# analog_part.net
KiCad netlist of a schematic drawn in Altium Designer
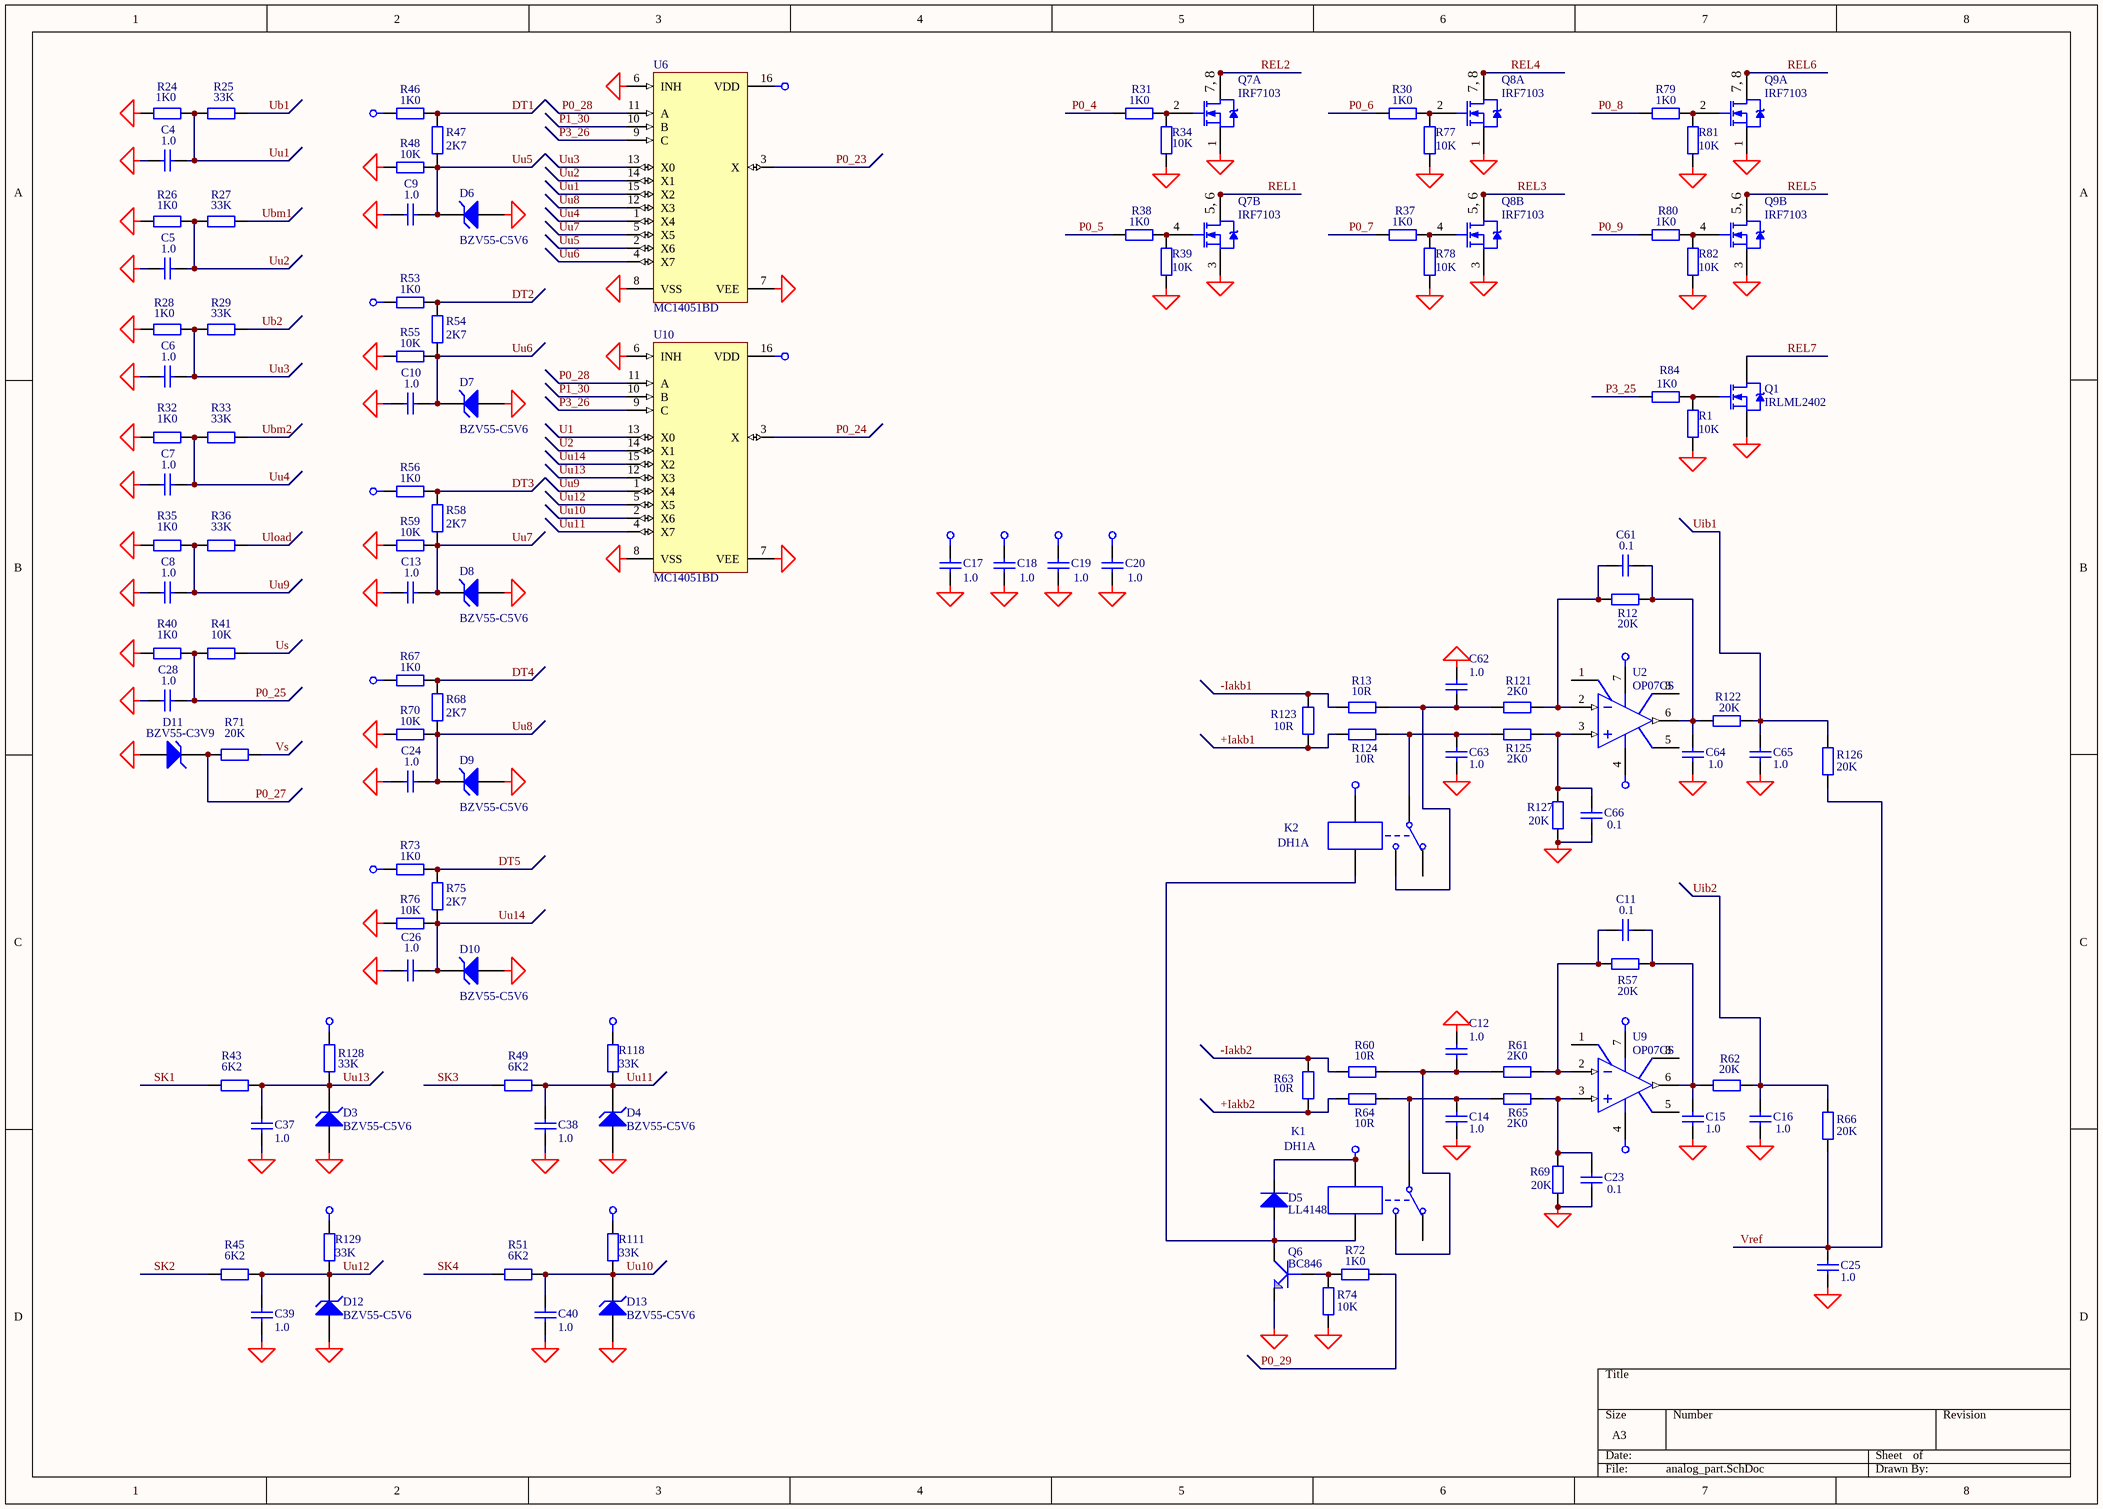
[diagram p0: analog_part.SchDoc]

(export (version "E")
  (design (tool "Eeschema 10.0.6"))
  (components
    (comp (ref "C4")
      (value "1.0")
      (footprint "_1206")
      (description "Capacitor")
      (fields (field (name "MANUFACTURER") "Generic Components"))
      (libsource (lib "Miscellaneous Devices") (part "Cap Semi"))
    )
    (comp (ref "C5")
      (value "1.0")
      (footprint "_1206")
      (description "Capacitor")
      (fields (field (name "MANUFACTURER") "Generic Components"))
      (libsource (lib "Miscellaneous Devices") (part "Cap Semi"))
    )
    (comp (ref "C6")
      (value "1.0")
      (footprint "_1206")
      (description "Capacitor")
      (fields (field (name "MANUFACTURER") "Generic Components"))
      (libsource (lib "Miscellaneous Devices") (part "Cap Semi"))
    )
    (comp (ref "C7")
      (value "1.0")
      (footprint "_1206")
      (description "Capacitor")
      (fields (field (name "MANUFACTURER") "Generic Components"))
      (libsource (lib "Miscellaneous Devices") (part "Cap Semi"))
    )
    (comp (ref "C8")
      (value "1.0")
      (footprint "_1206")
      (description "Capacitor")
      (fields (field (name "MANUFACTURER") "Generic Components"))
      (libsource (lib "Miscellaneous Devices") (part "Cap Semi"))
    )
    (comp (ref "C9")
      (value "1.0")
      (footprint "_1206")
      (description "Capacitor")
      (fields (field (name "MANUFACTURER") "Generic Components"))
      (libsource (lib "Miscellaneous Devices") (part "Cap Semi"))
    )
    (comp (ref "C10")
      (value "1.0")
      (footprint "_1206")
      (description "Capacitor")
      (fields (field (name "MANUFACTURER") "Generic Components"))
      (libsource (lib "Miscellaneous Devices") (part "Cap Semi"))
    )
    (comp (ref "C11")
      (value "0.1")
      (footprint "_1206")
      (description "Capacitor")
      (fields (field (name "MANUFACTURER") "Generic Components"))
      (libsource (lib "Miscellaneous Devices") (part "Cap Semi"))
    )
    (comp (ref "C12")
      (value "1.0")
      (footprint "_1206")
      (description "Capacitor")
      (fields (field (name "MANUFACTURER") "Generic Components"))
      (libsource (lib "Miscellaneous Devices") (part "Cap Semi"))
    )
    (comp (ref "C13")
      (value "1.0")
      (footprint "_1206")
      (description "Capacitor")
      (fields (field (name "MANUFACTURER") "Generic Components"))
      (libsource (lib "Miscellaneous Devices") (part "Cap Semi"))
    )
    (comp (ref "C14")
      (value "1.0")
      (footprint "_1206")
      (description "Capacitor")
      (fields (field (name "MANUFACTURER") "Generic Components"))
      (libsource (lib "Miscellaneous Devices") (part "Cap Semi"))
    )
    (comp (ref "C15")
      (value "1.0")
      (footprint "_1206")
      (description "Capacitor")
      (fields (field (name "MANUFACTURER") "Generic Components"))
      (libsource (lib "Miscellaneous Devices") (part "Cap Semi"))
    )
    (comp (ref "C16")
      (value "1.0")
      (footprint "_1206")
      (description "Capacitor")
      (fields (field (name "MANUFACTURER") "Generic Components"))
      (libsource (lib "Miscellaneous Devices") (part "Cap Semi"))
    )
    (comp (ref "C17")
      (value "1.0")
      (footprint "_1206")
      (description "Capacitor")
      (fields (field (name "MANUFACTURER") "Generic Components"))
      (libsource (lib "Miscellaneous Devices") (part "Cap Semi"))
    )
    (comp (ref "C18")
      (value "1.0")
      (footprint "_1206")
      (description "Capacitor")
      (fields (field (name "MANUFACTURER") "Generic Components"))
      (libsource (lib "Miscellaneous Devices") (part "Cap Semi"))
    )
    (comp (ref "C19")
      (value "1.0")
      (footprint "_1206")
      (description "Capacitor")
      (fields (field (name "MANUFACTURER") "Generic Components"))
      (libsource (lib "Miscellaneous Devices") (part "Cap Semi"))
    )
    (comp (ref "C20")
      (value "1.0")
      (footprint "_1206")
      (description "Capacitor")
      (fields (field (name "MANUFACTURER") "Generic Components"))
      (libsource (lib "Miscellaneous Devices") (part "Cap Semi"))
    )
    (comp (ref "C23")
      (value "0.1")
      (footprint "_1206")
      (description "Capacitor")
      (fields (field (name "MANUFACTURER") "Generic Components"))
      (libsource (lib "Miscellaneous Devices") (part "Cap Semi"))
    )
    (comp (ref "C24")
      (value "1.0")
      (footprint "_1206")
      (description "Capacitor")
      (fields (field (name "MANUFACTURER") "Generic Components"))
      (libsource (lib "Miscellaneous Devices") (part "Cap Semi"))
    )
    (comp (ref "C25")
      (value "1.0")
      (footprint "_1206")
      (description "Capacitor")
      (fields (field (name "MANUFACTURER") "Generic Components"))
      (libsource (lib "Miscellaneous Devices") (part "Cap Semi"))
    )
    (comp (ref "C26")
      (value "1.0")
      (footprint "_1206")
      (description "Capacitor")
      (fields (field (name "MANUFACTURER") "Generic Components"))
      (libsource (lib "Miscellaneous Devices") (part "Cap Semi"))
    )
    (comp (ref "C28")
      (value "1.0")
      (footprint "_1206")
      (description "Capacitor")
      (fields (field (name "MANUFACTURER") "Generic Components"))
      (libsource (lib "Miscellaneous Devices") (part "Cap Semi"))
    )
    (comp (ref "C37")
      (value "1.0")
      (footprint "_1206")
      (description "Capacitor")
      (fields (field (name "MANUFACTURER") "Generic Components"))
      (libsource (lib "Miscellaneous Devices") (part "Cap Semi"))
    )
    (comp (ref "C38")
      (value "1.0")
      (footprint "_1206")
      (description "Capacitor")
      (fields (field (name "MANUFACTURER") "Generic Components"))
      (libsource (lib "Miscellaneous Devices") (part "Cap Semi"))
    )
    (comp (ref "C39")
      (value "1.0")
      (footprint "_1206")
      (description "Capacitor")
      (fields (field (name "MANUFACTURER") "Generic Components"))
      (libsource (lib "Miscellaneous Devices") (part "Cap Semi"))
    )
    (comp (ref "C40")
      (value "1.0")
      (footprint "_1206")
      (description "Capacitor")
      (fields (field (name "MANUFACTURER") "Generic Components"))
      (libsource (lib "Miscellaneous Devices") (part "Cap Semi"))
    )
    (comp (ref "C61")
      (value "0.1")
      (footprint "_1206")
      (description "Capacitor")
      (fields (field (name "MANUFACTURER") "Generic Components"))
      (libsource (lib "Miscellaneous Devices") (part "Cap Semi"))
    )
    (comp (ref "C62")
      (value "1.0")
      (footprint "_1206")
      (description "Capacitor")
      (fields (field (name "MANUFACTURER") "Generic Components"))
      (libsource (lib "Miscellaneous Devices") (part "Cap Semi"))
    )
    (comp (ref "C63")
      (value "1.0")
      (footprint "_1206")
      (description "Capacitor")
      (fields (field (name "MANUFACTURER") "Generic Components"))
      (libsource (lib "Miscellaneous Devices") (part "Cap Semi"))
    )
    (comp (ref "C64")
      (value "1.0")
      (footprint "_1206")
      (description "Capacitor")
      (fields (field (name "MANUFACTURER") "Generic Components"))
      (libsource (lib "Miscellaneous Devices") (part "Cap Semi"))
    )
    (comp (ref "C65")
      (value "1.0")
      (footprint "_1206")
      (description "Capacitor")
      (fields (field (name "MANUFACTURER") "Generic Components"))
      (libsource (lib "Miscellaneous Devices") (part "Cap Semi"))
    )
    (comp (ref "C66")
      (value "0.1")
      (footprint "_1206")
      (description "Capacitor")
      (fields (field (name "MANUFACTURER") "Generic Components"))
      (libsource (lib "Miscellaneous Devices") (part "Cap Semi"))
    )
    (comp (ref "D3")
      (value "BZV55-C5V6")
      (footprint "_1206d")
      (description "Zener Diode")
      (fields (field (name "MANUFACTURER") "Generic Components"))
      (libsource (lib "Miscellaneous Devices") (part "D Zener"))
    )
    (comp (ref "D4")
      (value "BZV55-C5V6")
      (footprint "_1206d")
      (description "Zener Diode")
      (fields (field (name "MANUFACTURER") "Generic Components"))
      (libsource (lib "Miscellaneous Devices") (part "D Zener"))
    )
    (comp (ref "D5")
      (value "LL4148")
      (footprint "_1206d")
      (description "Diode")
      (fields (field (name "MANUFACTURER") "Generic Components"))
      (libsource (lib "Pal") (part "Diode"))
    )
    (comp (ref "D6")
      (value "BZV55-C5V6")
      (footprint "_1206d")
      (description "Zener Diode")
      (fields (field (name "MANUFACTURER") "Generic Components"))
      (libsource (lib "Miscellaneous Devices") (part "D Zener"))
    )
    (comp (ref "D7")
      (value "BZV55-C5V6")
      (footprint "_1206d")
      (description "Zener Diode")
      (fields (field (name "MANUFACTURER") "Generic Components"))
      (libsource (lib "Miscellaneous Devices") (part "D Zener"))
    )
    (comp (ref "D8")
      (value "BZV55-C5V6")
      (footprint "_1206d")
      (description "Zener Diode")
      (fields (field (name "MANUFACTURER") "Generic Components"))
      (libsource (lib "Miscellaneous Devices") (part "D Zener"))
    )
    (comp (ref "D9")
      (value "BZV55-C5V6")
      (footprint "_1206d")
      (description "Zener Diode")
      (fields (field (name "MANUFACTURER") "Generic Components"))
      (libsource (lib "Miscellaneous Devices") (part "D Zener"))
    )
    (comp (ref "D10")
      (value "BZV55-C5V6")
      (footprint "_1206d")
      (description "Zener Diode")
      (fields (field (name "MANUFACTURER") "Generic Components"))
      (libsource (lib "Miscellaneous Devices") (part "D Zener"))
    )
    (comp (ref "D11")
      (value "BZV55-C3V9")
      (footprint "_1206d")
      (description "Zener Diode")
      (fields (field (name "MANUFACTURER") "Generic Components"))
      (libsource (lib "Miscellaneous Devices") (part "D Zener"))
    )
    (comp (ref "D12")
      (value "BZV55-C5V6")
      (footprint "_1206d")
      (description "Zener Diode")
      (fields (field (name "MANUFACTURER") "Generic Components"))
      (libsource (lib "Miscellaneous Devices") (part "D Zener"))
    )
    (comp (ref "D13")
      (value "BZV55-C5V6")
      (footprint "_1206d")
      (description "Zener Diode")
      (fields (field (name "MANUFACTURER") "Generic Components"))
      (libsource (lib "Miscellaneous Devices") (part "D Zener"))
    )
    (comp (ref "K1")
      (value "DH1A")
      (footprint "kuan")
      (description "Relay")
      (fields (field (name "MANUFACTURER") "Generic Components"))
      (libsource (lib "PAL") (part "BS115"))
    )
    (comp (ref "K2")
      (value "DH1A")
      (footprint "kuan")
      (description "Relay")
      (fields (field (name "MANUFACTURER") "Generic Components"))
      (libsource (lib "PAL") (part "BS115"))
    )
    (comp (ref "Q1")
      (value "IRLML2402")
      (footprint "SO-G3/Z3.3")
      (description "HEXFET Power MOSFET")
      (fields (field (name "MANUFACTURER") "International Rectifier"))
      (libsource (lib "IR Discrete MOSFET") (part "IRLML2402"))
    )
    (comp (ref "Q6")
      (value "BC846")
      (footprint "SO-G3")
      (description "Bipolar transistor")
      (libsource (lib "MAIN") (part "GT122"))
    )
    (comp (ref "Q7")
      (value "IRF7103")
      (footprint "SO-G8/Y2.2")
      (description "FET")
      (fields (field (name "MANUFACTURER") "International Rectifier"))
      (libsource (lib "IR Discrete MOSFET") (part "IRF7301"))
    )
    (comp (ref "Q8")
      (value "IRF7103")
      (footprint "SO-G8/Y2.2")
      (description "FET")
      (fields (field (name "MANUFACTURER") "International Rectifier"))
      (libsource (lib "IR Discrete MOSFET") (part "IRF7301"))
    )
    (comp (ref "Q9")
      (value "IRF7103")
      (footprint "SO-G8/Y2.2")
      (description "FET")
      (fields (field (name "MANUFACTURER") "International Rectifier"))
      (libsource (lib "IR Discrete MOSFET") (part "IRF7301"))
    )
    (comp (ref "R1")
      (value "10K")
      (footprint "_1206")
      (description "Resistor")
      (fields (field (name "MANUFACTURER") "Generic Components"))
      (libsource (lib "") (part "Res2_1"))
    )
    (comp (ref "R12")
      (value "20K")
      (footprint "_1206")
      (description "Resistor")
      (fields (field (name "MANUFACTURER") "Generic Components"))
      (libsource (lib "Miscellaneous Devices") (part "Res2"))
    )
    (comp (ref "R13")
      (value "10R")
      (footprint "_1206")
      (description "Resistor")
      (fields (field (name "MANUFACTURER") "Generic Components"))
      (libsource (lib "") (part "Res2_2"))
    )
    (comp (ref "R24")
      (value "1K0")
      (footprint "_1206")
      (description "Resistor")
      (fields (field (name "MANUFACTURER") "Generic Components"))
      (libsource (lib "") (part "Res2_2"))
    )
    (comp (ref "R25")
      (value "33K")
      (footprint "_1206")
      (description "Resistor")
      (fields (field (name "MANUFACTURER") "Generic Components"))
      (libsource (lib "Miscellaneous Devices") (part "Res2"))
    )
    (comp (ref "R26")
      (value "1K0")
      (footprint "_1206")
      (description "Resistor")
      (fields (field (name "MANUFACTURER") "Generic Components"))
      (libsource (lib "") (part "Res2_2"))
    )
    (comp (ref "R27")
      (value "33K")
      (footprint "_1206")
      (description "Resistor")
      (fields (field (name "MANUFACTURER") "Generic Components"))
      (libsource (lib "Miscellaneous Devices") (part "Res2"))
    )
    (comp (ref "R28")
      (value "1K0")
      (footprint "_1206")
      (description "Resistor")
      (fields (field (name "MANUFACTURER") "Generic Components"))
      (libsource (lib "") (part "Res2_2"))
    )
    (comp (ref "R29")
      (value "33K")
      (footprint "_1206")
      (description "Resistor")
      (fields (field (name "MANUFACTURER") "Generic Components"))
      (libsource (lib "Miscellaneous Devices") (part "Res2"))
    )
    (comp (ref "R30")
      (value "1K0")
      (footprint "_1206")
      (description "Resistor")
      (fields (field (name "MANUFACTURER") "Generic Components"))
      (libsource (lib "Miscellaneous Devices") (part "Res2"))
    )
    (comp (ref "R31")
      (value "1K0")
      (footprint "_1206")
      (description "Resistor")
      (fields (field (name "MANUFACTURER") "Generic Components"))
      (libsource (lib "Miscellaneous Devices") (part "Res2"))
    )
    (comp (ref "R32")
      (value "1K0")
      (footprint "_1206")
      (description "Resistor")
      (fields (field (name "MANUFACTURER") "Generic Components"))
      (libsource (lib "") (part "Res2_2"))
    )
    (comp (ref "R33")
      (value "33K")
      (footprint "_1206")
      (description "Resistor")
      (fields (field (name "MANUFACTURER") "Generic Components"))
      (libsource (lib "Miscellaneous Devices") (part "Res2"))
    )
    (comp (ref "R34")
      (value "10K")
      (footprint "_1206")
      (description "Resistor")
      (fields (field (name "MANUFACTURER") "Generic Components"))
      (libsource (lib "") (part "Res2_1"))
    )
    (comp (ref "R35")
      (value "1K0")
      (footprint "_1206")
      (description "Resistor")
      (fields (field (name "MANUFACTURER") "Generic Components"))
      (libsource (lib "") (part "Res2_2"))
    )
    (comp (ref "R36")
      (value "33K")
      (footprint "_1206")
      (description "Resistor")
      (fields (field (name "MANUFACTURER") "Generic Components"))
      (libsource (lib "Miscellaneous Devices") (part "Res2"))
    )
    (comp (ref "R37")
      (value "1K0")
      (footprint "_1206")
      (description "Resistor")
      (fields (field (name "MANUFACTURER") "Generic Components") (field (name "ALTIUM_VALUE") "1K0"))
      (libsource (lib "Miscellaneous Devices") (part "Res2"))
    )
    (comp (ref "R38")
      (value "1K0")
      (footprint "_1206")
      (description "Resistor")
      (fields (field (name "MANUFACTURER") "Generic Components"))
      (libsource (lib "Miscellaneous Devices") (part "Res2"))
    )
    (comp (ref "R39")
      (value "10K")
      (footprint "_1206")
      (description "Resistor")
      (fields (field (name "MANUFACTURER") "Generic Components"))
      (libsource (lib "") (part "Res2_1"))
    )
    (comp (ref "R40")
      (value "1K0")
      (footprint "_1206")
      (description "Resistor")
      (fields (field (name "MANUFACTURER") "Generic Components"))
      (libsource (lib "") (part "Res2_2"))
    )
    (comp (ref "R41")
      (value "10K")
      (footprint "_1206")
      (description "Resistor")
      (fields (field (name "MANUFACTURER") "Generic Components"))
      (libsource (lib "Miscellaneous Devices") (part "Res2"))
    )
    (comp (ref "R43")
      (value "6K2")
      (footprint "_1206")
      (description "Resistor")
      (fields (field (name "MANUFACTURER") "Generic Components"))
      (libsource (lib "Miscellaneous Devices") (part "Res2"))
    )
    (comp (ref "R45")
      (value "6K2")
      (footprint "_1206")
      (description "Resistor")
      (fields (field (name "MANUFACTURER") "Generic Components"))
      (libsource (lib "Miscellaneous Devices") (part "Res2"))
    )
    (comp (ref "R46")
      (value "1K0")
      (footprint "_0805")
      (description "Resistor")
      (fields (field (name "MANUFACTURER") "Generic Components"))
      (libsource (lib "") (part "Res2_2"))
    )
    (comp (ref "R47")
      (value "2K7")
      (footprint "_1206")
      (description "Resistor")
      (fields (field (name "MANUFACTURER") "Generic Components"))
      (libsource (lib "") (part "Res2_3"))
    )
    (comp (ref "R48")
      (value "10K")
      (footprint "_1206")
      (description "Resistor")
      (fields (field (name "MANUFACTURER") "Generic Components"))
      (libsource (lib "Miscellaneous Devices") (part "Res2"))
    )
    (comp (ref "R49")
      (value "6K2")
      (footprint "_1206")
      (description "Resistor")
      (fields (field (name "MANUFACTURER") "Generic Components"))
      (libsource (lib "Miscellaneous Devices") (part "Res2"))
    )
    (comp (ref "R51")
      (value "6K2")
      (footprint "_1206")
      (description "Resistor")
      (fields (field (name "MANUFACTURER") "Generic Components"))
      (libsource (lib "Miscellaneous Devices") (part "Res2"))
    )
    (comp (ref "R53")
      (value "1K0")
      (footprint "_0805")
      (description "Resistor")
      (fields (field (name "MANUFACTURER") "Generic Components") (field (name "ALTIUM_VALUE") "1K0"))
      (libsource (lib "") (part "Res2_2"))
    )
    (comp (ref "R54")
      (value "2K7")
      (footprint "_1206")
      (description "Resistor")
      (fields (field (name "MANUFACTURER") "Generic Components"))
      (libsource (lib "") (part "Res2_3"))
    )
    (comp (ref "R55")
      (value "10K")
      (footprint "_1206")
      (description "Resistor")
      (fields (field (name "MANUFACTURER") "Generic Components"))
      (libsource (lib "Miscellaneous Devices") (part "Res2"))
    )
    (comp (ref "R56")
      (value "1K0")
      (footprint "_0805")
      (description "Resistor")
      (fields (field (name "MANUFACTURER") "Generic Components") (field (name "ALTIUM_VALUE") "1K0"))
      (libsource (lib "") (part "Res2_2"))
    )
    (comp (ref "R57")
      (value "20K")
      (footprint "_1206")
      (description "Resistor")
      (fields (field (name "MANUFACTURER") "Generic Components"))
      (libsource (lib "Miscellaneous Devices") (part "Res2"))
    )
    (comp (ref "R58")
      (value "2K7")
      (footprint "_1206")
      (description "Resistor")
      (fields (field (name "MANUFACTURER") "Generic Components"))
      (libsource (lib "") (part "Res2_3"))
    )
    (comp (ref "R59")
      (value "10K")
      (footprint "_1206")
      (description "Resistor")
      (fields (field (name "MANUFACTURER") "Generic Components"))
      (libsource (lib "Miscellaneous Devices") (part "Res2"))
    )
    (comp (ref "R60")
      (value "10R")
      (footprint "_1206")
      (description "Resistor")
      (fields (field (name "MANUFACTURER") "Generic Components"))
      (libsource (lib "") (part "Res2_2"))
    )
    (comp (ref "R61")
      (value "2K0")
      (footprint "_1206")
      (description "Resistor")
      (fields (field (name "MANUFACTURER") "Generic Components"))
      (libsource (lib "Miscellaneous Devices") (part "Res2"))
    )
    (comp (ref "R62")
      (value "20K")
      (footprint "_1206")
      (description "Resistor")
      (fields (field (name "MANUFACTURER") "Generic Components"))
      (libsource (lib "Miscellaneous Devices") (part "Res2"))
    )
    (comp (ref "R63")
      (value "10R")
      (footprint "_1206")
      (description "Resistor")
      (fields (field (name "MANUFACTURER") "Generic Components"))
      (libsource (lib "") (part "Res2_1"))
    )
    (comp (ref "R64")
      (value "10R")
      (footprint "_1206")
      (description "Resistor")
      (fields (field (name "MANUFACTURER") "Generic Components"))
      (libsource (lib "") (part "Res2_2"))
    )
    (comp (ref "R65")
      (value "2K0")
      (footprint "_1206")
      (description "Resistor")
      (fields (field (name "MANUFACTURER") "Generic Components"))
      (libsource (lib "Miscellaneous Devices") (part "Res2"))
    )
    (comp (ref "R66")
      (value "20K")
      (footprint "_1206")
      (description "Resistor")
      (fields (field (name "MANUFACTURER") "Generic Components"))
      (libsource (lib "") (part "Res2_2"))
    )
    (comp (ref "R67")
      (value "1K0")
      (footprint "_0805")
      (description "Resistor")
      (fields (field (name "MANUFACTURER") "Generic Components") (field (name "ALTIUM_VALUE") "1K0"))
      (libsource (lib "") (part "Res2_2"))
    )
    (comp (ref "R68")
      (value "2K7")
      (footprint "_1206")
      (description "Resistor")
      (fields (field (name "MANUFACTURER") "Generic Components"))
      (libsource (lib "") (part "Res2_3"))
    )
    (comp (ref "R69")
      (value "20K")
      (footprint "_1206")
      (description "Resistor")
      (fields (field (name "MANUFACTURER") "Generic Components"))
      (libsource (lib "") (part "Res2_1"))
    )
    (comp (ref "R70")
      (value "10K")
      (footprint "_1206")
      (description "Resistor")
      (fields (field (name "MANUFACTURER") "Generic Components"))
      (libsource (lib "Miscellaneous Devices") (part "Res2"))
    )
    (comp (ref "R71")
      (value "20K")
      (footprint "_1206")
      (description "Resistor")
      (fields (field (name "MANUFACTURER") "Generic Components"))
      (libsource (lib "Miscellaneous Devices") (part "Res2"))
    )
    (comp (ref "R72")
      (value "1K0")
      (footprint "_1206")
      (description "Resistor")
      (fields (field (name "MANUFACTURER") "Generic Components"))
      (libsource (lib "") (part "Res2_3"))
    )
    (comp (ref "R73")
      (value "1K0")
      (footprint "_0805")
      (description "Resistor")
      (fields (field (name "MANUFACTURER") "Generic Components") (field (name "ALTIUM_VALUE") "1K0"))
      (libsource (lib "") (part "Res2_2"))
    )
    (comp (ref "R74")
      (value "10K")
      (footprint "_1206")
      (description "Resistor")
      (fields (field (name "MANUFACTURER") "Generic Components"))
      (libsource (lib "Miscellaneous Devices") (part "Res2"))
    )
    (comp (ref "R75")
      (value "2K7")
      (footprint "_1206")
      (description "Resistor")
      (fields (field (name "MANUFACTURER") "Generic Components"))
      (libsource (lib "") (part "Res2_3"))
    )
    (comp (ref "R76")
      (value "10K")
      (footprint "_1206")
      (description "Resistor")
      (fields (field (name "MANUFACTURER") "Generic Components"))
      (libsource (lib "Miscellaneous Devices") (part "Res2"))
    )
    (comp (ref "R77")
      (value "10K")
      (footprint "_1206")
      (description "Resistor")
      (fields (field (name "MANUFACTURER") "Generic Components"))
      (libsource (lib "") (part "Res2_1"))
    )
    (comp (ref "R78")
      (value "10K")
      (footprint "_1206")
      (description "Resistor")
      (fields (field (name "MANUFACTURER") "Generic Components"))
      (libsource (lib "") (part "Res2_1"))
    )
    (comp (ref "R79")
      (value "1K0")
      (footprint "_1206")
      (description "Resistor")
      (fields (field (name "MANUFACTURER") "Generic Components"))
      (libsource (lib "Miscellaneous Devices") (part "Res2"))
    )
    (comp (ref "R80")
      (value "1K0")
      (footprint "_1206")
      (description "Resistor")
      (fields (field (name "MANUFACTURER") "Generic Components") (field (name "ALTIUM_VALUE") "1K0"))
      (libsource (lib "Miscellaneous Devices") (part "Res2"))
    )
    (comp (ref "R81")
      (value "10K")
      (footprint "_1206")
      (description "Resistor")
      (fields (field (name "MANUFACTURER") "Generic Components"))
      (libsource (lib "") (part "Res2_1"))
    )
    (comp (ref "R82")
      (value "10K")
      (footprint "_1206")
      (description "Resistor")
      (fields (field (name "MANUFACTURER") "Generic Components"))
      (libsource (lib "") (part "Res2_1"))
    )
    (comp (ref "R84")
      (value "1K0")
      (footprint "_1206")
      (description "Resistor")
      (fields (field (name "MANUFACTURER") "Generic Components"))
      (libsource (lib "Miscellaneous Devices") (part "Res2"))
    )
    (comp (ref "R111")
      (value "33K")
      (footprint "_1206")
      (description "Resistor")
      (fields (field (name "MANUFACTURER") "Generic Components"))
      (libsource (lib "") (part "Res2_2"))
    )
    (comp (ref "R118")
      (value "33K")
      (footprint "_1206")
      (description "Resistor")
      (fields (field (name "MANUFACTURER") "Generic Components"))
      (libsource (lib "") (part "Res2_2"))
    )
    (comp (ref "R121")
      (value "2K0")
      (footprint "_1206")
      (description "Resistor")
      (fields (field (name "MANUFACTURER") "Generic Components"))
      (libsource (lib "Miscellaneous Devices") (part "Res2"))
    )
    (comp (ref "R122")
      (value "20K")
      (footprint "_1206")
      (description "Resistor")
      (fields (field (name "MANUFACTURER") "Generic Components"))
      (libsource (lib "Miscellaneous Devices") (part "Res2"))
    )
    (comp (ref "R123")
      (value "10R")
      (footprint "_1206")
      (description "Resistor")
      (fields (field (name "MANUFACTURER") "Generic Components"))
      (libsource (lib "") (part "Res2_1"))
    )
    (comp (ref "R124")
      (value "10R")
      (footprint "_1206")
      (description "Resistor")
      (fields (field (name "MANUFACTURER") "Generic Components"))
      (libsource (lib "") (part "Res2_2"))
    )
    (comp (ref "R125")
      (value "2K0")
      (footprint "_1206")
      (description "Resistor")
      (fields (field (name "MANUFACTURER") "Generic Components"))
      (libsource (lib "Miscellaneous Devices") (part "Res2"))
    )
    (comp (ref "R126")
      (value "20K")
      (footprint "_1206")
      (description "Resistor")
      (fields (field (name "MANUFACTURER") "Generic Components"))
      (libsource (lib "") (part "Res2_2"))
    )
    (comp (ref "R127")
      (value "20K")
      (footprint "_1206")
      (description "Resistor")
      (fields (field (name "MANUFACTURER") "Generic Components"))
      (libsource (lib "") (part "Res2_1"))
    )
    (comp (ref "R128")
      (value "33K")
      (footprint "_1206")
      (description "Resistor")
      (fields (field (name "MANUFACTURER") "Generic Components"))
      (libsource (lib "") (part "Res2_3"))
    )
    (comp (ref "R129")
      (value "33K")
      (footprint "_1206")
      (description "Resistor")
      (fields (field (name "MANUFACTURER") "Generic Components"))
      (libsource (lib "") (part "Res2_2"))
    )
    (comp (ref "U2")
      (value "OP07CS")
      (footprint "SO-G8")
      (description "Operational Amplifier")
      (fields (field (name "MANUFACTURER") "Analog Devices"))
      (libsource (lib "AD Operational Amplifier") (part "OP07CS"))
    )
    (comp (ref "U6")
      (value "MC14051BD")
      (footprint "SO-G16/C5.85")
      (description "Multiplexer")
      (fields (field (name "MANUFACTURER") "ON Semiconductor"))
      (libsource (lib "ON Semi Logic Multiplexer") (part "MC14051BD"))
    )
    (comp (ref "U9")
      (value "OP07CS")
      (footprint "SO-G8")
      (description "Operational Amplifier")
      (fields (field (name "MANUFACTURER") "Analog Devices"))
      (libsource (lib "AD Operational Amplifier") (part "OP07CS"))
    )
    (comp (ref "U10")
      (value "MC14051BD")
      (footprint "SO-G16/C5.85")
      (description "Multiplexer")
      (fields (field (name "MANUFACTURER") "ON Semiconductor"))
      (libsource (lib "ON Semi Logic Multiplexer") (part "MC14051BD"))
    )
  )
  (nets
    (net (code "1") (name "+3v3") (class "Default")
      (node (ref "R111") (pin "1") (pinfunction "1_1") (pintype "passive"))
      (node (ref "R118") (pin "1") (pinfunction "1_1") (pintype "passive"))
      (node (ref "R128") (pin "1") (pinfunction "1_1") (pintype "passive"))
      (node (ref "R129") (pin "1") (pinfunction "1_1") (pintype "passive"))
    )
    (net (code "2") (name "+5v") (class "Default")
      (node (ref "C17") (pin "2") (pinfunction "2_2") (pintype "passive"))
      (node (ref "C19") (pin "2") (pinfunction "2_2") (pintype "passive"))
      (node (ref "D5") (pin "2") (pinfunction "K_2") (pintype "passive"))
      (node (ref "K1") (pin "4") (pinfunction "4_4") (pintype "passive"))
      (node (ref "K2") (pin "4") (pinfunction "4_4") (pintype "passive"))
      (node (ref "R46") (pin "2") (pinfunction "2_2") (pintype "passive"))
      (node (ref "R53") (pin "2") (pinfunction "2_2") (pintype "passive"))
      (node (ref "R56") (pin "2") (pinfunction "2_2") (pintype "passive"))
      (node (ref "R67") (pin "2") (pinfunction "2_2") (pintype "passive"))
      (node (ref "R73") (pin "2") (pinfunction "2_2") (pintype "passive"))
      (node (ref "U10") (pin "16") (pinfunction "VDD_16") (pintype "power_in"))
      (node (ref "U2") (pin "7") (pinfunction "V+_7") (pintype "power_in"))
      (node (ref "U6") (pin "16") (pinfunction "VDD_16") (pintype "power_in"))
      (node (ref "U9") (pin "7") (pinfunction "V+_7") (pintype "power_in"))
    )
    (net (code "3") (name "-5v") (class "Default")
      (node (ref "C18") (pin "2") (pinfunction "2_2") (pintype "passive"))
      (node (ref "U2") (pin "4") (pinfunction "V-_4") (pintype "power_in"))
      (node (ref "U9") (pin "4") (pinfunction "V-_4") (pintype "power_in"))
    )
    (net (code "4") (name "/+Iakb1") (class "Default")
      (node (ref "R123") (pin "1") (pinfunction "1_1") (pintype "passive"))
      (node (ref "R124") (pin "2") (pinfunction "2_2") (pintype "passive"))
    )
    (net (code "5") (name "/+Iakb2") (class "Default")
      (node (ref "R63") (pin "1") (pinfunction "1_1") (pintype "passive"))
      (node (ref "R64") (pin "2") (pinfunction "2_2") (pintype "passive"))
    )
    (net (code "6") (name "/-Iakb1") (class "Default")
      (node (ref "R123") (pin "2") (pinfunction "2_2") (pintype "passive"))
      (node (ref "R13") (pin "2") (pinfunction "2_2") (pintype "passive"))
    )
    (net (code "7") (name "/-Iakb2") (class "Default")
      (node (ref "R60") (pin "2") (pinfunction "2_2") (pintype "passive"))
      (node (ref "R63") (pin "2") (pinfunction "2_2") (pintype "passive"))
    )
    (net (code "8") (name "/DT1") (class "Default")
      (node (ref "R46") (pin "1") (pinfunction "1_1") (pintype "passive"))
      (node (ref "R47") (pin "1") (pinfunction "1_1") (pintype "passive"))
    )
    (net (code "9") (name "/DT2") (class "Default")
      (node (ref "R53") (pin "1") (pinfunction "1_1") (pintype "passive"))
      (node (ref "R54") (pin "1") (pinfunction "1_1") (pintype "passive"))
    )
    (net (code "10") (name "/DT3") (class "Default")
      (node (ref "R56") (pin "1") (pinfunction "1_1") (pintype "passive"))
      (node (ref "R58") (pin "1") (pinfunction "1_1") (pintype "passive"))
    )
    (net (code "11") (name "/DT4") (class "Default")
      (node (ref "R67") (pin "1") (pinfunction "1_1") (pintype "passive"))
      (node (ref "R68") (pin "1") (pinfunction "1_1") (pintype "passive"))
    )
    (net (code "12") (name "/DT5") (class "Default")
      (node (ref "R73") (pin "1") (pinfunction "1_1") (pintype "passive"))
      (node (ref "R75") (pin "1") (pinfunction "1_1") (pintype "passive"))
    )
    (net (code "13") (name "/P0_4") (class "Default")
      (node (ref "R31") (pin "1") (pinfunction "1_1") (pintype "passive"))
    )
    (net (code "14") (name "/P0_5") (class "Default")
      (node (ref "R38") (pin "1") (pinfunction "1_1") (pintype "passive"))
    )
    (net (code "15") (name "/P0_6") (class "Default")
      (node (ref "R30") (pin "1") (pinfunction "1_1") (pintype "passive"))
    )
    (net (code "16") (name "/P0_7") (class "Default")
      (node (ref "R37") (pin "1") (pinfunction "1_1") (pintype "passive"))
    )
    (net (code "17") (name "/P0_8") (class "Default")
      (node (ref "R79") (pin "1") (pinfunction "1_1") (pintype "passive"))
    )
    (net (code "18") (name "/P0_9") (class "Default")
      (node (ref "R80") (pin "1") (pinfunction "1_1") (pintype "passive"))
    )
    (net (code "19") (name "/P0_23") (class "Default")
      (node (ref "U6") (pin "3") (pinfunction "X_3") (pintype "bidirectional"))
    )
    (net (code "20") (name "/P0_24") (class "Default")
      (node (ref "U10") (pin "3") (pinfunction "X_3") (pintype "bidirectional"))
    )
    (net (code "21") (name "/P0_25") (class "Default")
      (node (ref "C28") (pin "1") (pinfunction "1_1") (pintype "passive"))
      (node (ref "R40") (pin "1") (pinfunction "1_1") (pintype "passive"))
      (node (ref "R41") (pin "1") (pinfunction "1_1") (pintype "passive"))
    )
    (net (code "22") (name "/P0_27") (class "Default")
      (node (ref "D11") (pin "2") (pinfunction "K_2") (pintype "passive"))
      (node (ref "R71") (pin "1") (pinfunction "1_1") (pintype "passive"))
    )
    (net (code "23") (name "/P0_28") (class "Default")
      (node (ref "U10") (pin "11") (pinfunction "A_11") (pintype "input"))
      (node (ref "U6") (pin "11") (pinfunction "A_11") (pintype "input"))
    )
    (net (code "24") (name "/P0_29") (class "Default")
      (node (ref "R72") (pin "1") (pinfunction "1_1") (pintype "passive"))
    )
    (net (code "25") (name "/P1_30") (class "Default")
      (node (ref "U10") (pin "10") (pinfunction "B_10") (pintype "input"))
      (node (ref "U6") (pin "10") (pinfunction "B_10") (pintype "input"))
    )
    (net (code "26") (name "/P3_25") (class "Default")
      (node (ref "R84") (pin "1") (pinfunction "1_1") (pintype "passive"))
    )
    (net (code "27") (name "/P3_26") (class "Default")
      (node (ref "U10") (pin "9") (pinfunction "C_9") (pintype "input"))
      (node (ref "U6") (pin "9") (pinfunction "C_9") (pintype "input"))
    )
    (net (code "28") (name "/REL1") (class "Default")
      (node (ref "Q7") (pin "5") (pinfunction "D_5") (pintype "passive"))
      (node (ref "Q7") (pin "6") (pinfunction "D_6") (pintype "passive"))
    )
    (net (code "29") (name "/REL2") (class "Default")
      (node (ref "Q7") (pin "7") (pinfunction "D_7") (pintype "passive"))
      (node (ref "Q7") (pin "8") (pinfunction "D_8") (pintype "passive"))
    )
    (net (code "30") (name "/REL3") (class "Default")
      (node (ref "Q8") (pin "5") (pinfunction "D_5") (pintype "passive"))
      (node (ref "Q8") (pin "6") (pinfunction "D_6") (pintype "passive"))
    )
    (net (code "31") (name "/REL4") (class "Default")
      (node (ref "Q8") (pin "7") (pinfunction "D_7") (pintype "passive"))
      (node (ref "Q8") (pin "8") (pinfunction "D_8") (pintype "passive"))
    )
    (net (code "32") (name "/REL5") (class "Default")
      (node (ref "Q9") (pin "5") (pinfunction "D_5") (pintype "passive"))
      (node (ref "Q9") (pin "6") (pinfunction "D_6") (pintype "passive"))
    )
    (net (code "33") (name "/REL6") (class "Default")
      (node (ref "Q9") (pin "7") (pinfunction "D_7") (pintype "passive"))
      (node (ref "Q9") (pin "8") (pinfunction "D_8") (pintype "passive"))
    )
    (net (code "34") (name "/REL7") (class "Default")
      (node (ref "Q1") (pin "3") (pinfunction "D_3") (pintype "passive"))
    )
    (net (code "35") (name "/SK1") (class "Default")
      (node (ref "R43") (pin "1") (pinfunction "1_1") (pintype "passive"))
    )
    (net (code "36") (name "/SK2") (class "Default")
      (node (ref "R45") (pin "1") (pinfunction "1_1") (pintype "passive"))
    )
    (net (code "37") (name "/SK3") (class "Default")
      (node (ref "R49") (pin "1") (pinfunction "1_1") (pintype "passive"))
    )
    (net (code "38") (name "/SK4") (class "Default")
      (node (ref "R51") (pin "1") (pinfunction "1_1") (pintype "passive"))
    )
    (net (code "39") (name "/U1") (class "Default")
      (node (ref "U10") (pin "13") (pinfunction "X0_13") (pintype "bidirectional"))
    )
    (net (code "40") (name "/U2") (class "Default")
      (node (ref "U10") (pin "14") (pinfunction "X1_14") (pintype "bidirectional"))
    )
    (net (code "41") (name "/Ub1") (class "Default")
      (node (ref "R25") (pin "2") (pinfunction "2_2") (pintype "passive"))
    )
    (net (code "42") (name "/Ub2") (class "Default")
      (node (ref "R29") (pin "2") (pinfunction "2_2") (pintype "passive"))
    )
    (net (code "43") (name "/Ubm1") (class "Default")
      (node (ref "R27") (pin "2") (pinfunction "2_2") (pintype "passive"))
    )
    (net (code "44") (name "/Ubm2") (class "Default")
      (node (ref "R33") (pin "2") (pinfunction "2_2") (pintype "passive"))
    )
    (net (code "45") (name "/Uib1") (class "Default")
      (node (ref "C65") (pin "2") (pinfunction "2_2") (pintype "passive"))
      (node (ref "R122") (pin "2") (pinfunction "2_2") (pintype "passive"))
      (node (ref "R126") (pin "1") (pinfunction "1_1") (pintype "passive"))
    )
    (net (code "46") (name "/Uib2") (class "Default")
      (node (ref "C16") (pin "2") (pinfunction "2_2") (pintype "passive"))
      (node (ref "R62") (pin "2") (pinfunction "2_2") (pintype "passive"))
      (node (ref "R66") (pin "1") (pinfunction "1_1") (pintype "passive"))
    )
    (net (code "47") (name "/Uload") (class "Default")
      (node (ref "R36") (pin "2") (pinfunction "2_2") (pintype "passive"))
    )
    (net (code "48") (name "/Us") (class "Default")
      (node (ref "R41") (pin "2") (pinfunction "2_2") (pintype "passive"))
    )
    (net (code "49") (name "/Uu1") (class "Default")
      (node (ref "C4") (pin "1") (pinfunction "1_1") (pintype "passive"))
      (node (ref "R24") (pin "1") (pinfunction "1_1") (pintype "passive"))
      (node (ref "R25") (pin "1") (pinfunction "1_1") (pintype "passive"))
      (node (ref "U6") (pin "15") (pinfunction "X2_15") (pintype "bidirectional"))
    )
    (net (code "50") (name "/Uu2") (class "Default")
      (node (ref "C5") (pin "1") (pinfunction "1_1") (pintype "passive"))
      (node (ref "R26") (pin "1") (pinfunction "1_1") (pintype "passive"))
      (node (ref "R27") (pin "1") (pinfunction "1_1") (pintype "passive"))
      (node (ref "U6") (pin "14") (pinfunction "X1_14") (pintype "bidirectional"))
    )
    (net (code "51") (name "/Uu3") (class "Default")
      (node (ref "C6") (pin "1") (pinfunction "1_1") (pintype "passive"))
      (node (ref "R28") (pin "1") (pinfunction "1_1") (pintype "passive"))
      (node (ref "R29") (pin "1") (pinfunction "1_1") (pintype "passive"))
      (node (ref "U6") (pin "13") (pinfunction "X0_13") (pintype "bidirectional"))
    )
    (net (code "52") (name "/Uu4") (class "Default")
      (node (ref "C7") (pin "1") (pinfunction "1_1") (pintype "passive"))
      (node (ref "R32") (pin "1") (pinfunction "1_1") (pintype "passive"))
      (node (ref "R33") (pin "1") (pinfunction "1_1") (pintype "passive"))
      (node (ref "U6") (pin "1") (pinfunction "X4_1") (pintype "bidirectional"))
    )
    (net (code "53") (name "/Uu5") (class "Default")
      (node (ref "C9") (pin "1") (pinfunction "1_1") (pintype "passive"))
      (node (ref "D6") (pin "2") (pinfunction "K_2") (pintype "passive"))
      (node (ref "R47") (pin "2") (pinfunction "2_2") (pintype "passive"))
      (node (ref "R48") (pin "2") (pinfunction "2_2") (pintype "passive"))
      (node (ref "U6") (pin "2") (pinfunction "X6_2") (pintype "bidirectional"))
    )
    (net (code "54") (name "/Uu6") (class "Default")
      (node (ref "C10") (pin "1") (pinfunction "1_1") (pintype "passive"))
      (node (ref "D7") (pin "2") (pinfunction "K_2") (pintype "passive"))
      (node (ref "R54") (pin "2") (pinfunction "2_2") (pintype "passive"))
      (node (ref "R55") (pin "2") (pinfunction "2_2") (pintype "passive"))
      (node (ref "U6") (pin "4") (pinfunction "X7_4") (pintype "bidirectional"))
    )
    (net (code "55") (name "/Uu7") (class "Default")
      (node (ref "C13") (pin "1") (pinfunction "1_1") (pintype "passive"))
      (node (ref "D8") (pin "2") (pinfunction "K_2") (pintype "passive"))
      (node (ref "R58") (pin "2") (pinfunction "2_2") (pintype "passive"))
      (node (ref "R59") (pin "2") (pinfunction "2_2") (pintype "passive"))
      (node (ref "U6") (pin "5") (pinfunction "X5_5") (pintype "bidirectional"))
    )
    (net (code "56") (name "/Uu8") (class "Default")
      (node (ref "C24") (pin "1") (pinfunction "1_1") (pintype "passive"))
      (node (ref "D9") (pin "2") (pinfunction "K_2") (pintype "passive"))
      (node (ref "R68") (pin "2") (pinfunction "2_2") (pintype "passive"))
      (node (ref "R70") (pin "2") (pinfunction "2_2") (pintype "passive"))
      (node (ref "U6") (pin "12") (pinfunction "X3_12") (pintype "bidirectional"))
    )
    (net (code "57") (name "/Uu9") (class "Default")
      (node (ref "C8") (pin "1") (pinfunction "1_1") (pintype "passive"))
      (node (ref "R35") (pin "1") (pinfunction "1_1") (pintype "passive"))
      (node (ref "R36") (pin "1") (pinfunction "1_1") (pintype "passive"))
      (node (ref "U10") (pin "1") (pinfunction "X4_1") (pintype "bidirectional"))
    )
    (net (code "58") (name "/Uu10") (class "Default")
      (node (ref "C40") (pin "1") (pinfunction "1_1") (pintype "passive"))
      (node (ref "D13") (pin "2") (pinfunction "K_2") (pintype "passive"))
      (node (ref "R111") (pin "2") (pinfunction "2_2") (pintype "passive"))
      (node (ref "R51") (pin "2") (pinfunction "2_2") (pintype "passive"))
      (node (ref "U10") (pin "2") (pinfunction "X6_2") (pintype "bidirectional"))
    )
    (net (code "59") (name "/Uu11") (class "Default")
      (node (ref "C38") (pin "1") (pinfunction "1_1") (pintype "passive"))
      (node (ref "D4") (pin "2") (pinfunction "K_2") (pintype "passive"))
      (node (ref "R118") (pin "2") (pinfunction "2_2") (pintype "passive"))
      (node (ref "R49") (pin "2") (pinfunction "2_2") (pintype "passive"))
      (node (ref "U10") (pin "4") (pinfunction "X7_4") (pintype "bidirectional"))
    )
    (net (code "60") (name "/Uu12") (class "Default")
      (node (ref "C39") (pin "1") (pinfunction "1_1") (pintype "passive"))
      (node (ref "D12") (pin "2") (pinfunction "K_2") (pintype "passive"))
      (node (ref "R129") (pin "2") (pinfunction "2_2") (pintype "passive"))
      (node (ref "R45") (pin "2") (pinfunction "2_2") (pintype "passive"))
      (node (ref "U10") (pin "5") (pinfunction "X5_5") (pintype "bidirectional"))
    )
    (net (code "61") (name "/Uu13") (class "Default")
      (node (ref "C37") (pin "1") (pinfunction "1_1") (pintype "passive"))
      (node (ref "D3") (pin "2") (pinfunction "K_2") (pintype "passive"))
      (node (ref "R128") (pin "2") (pinfunction "2_2") (pintype "passive"))
      (node (ref "R43") (pin "2") (pinfunction "2_2") (pintype "passive"))
      (node (ref "U10") (pin "12") (pinfunction "X3_12") (pintype "bidirectional"))
    )
    (net (code "62") (name "/Uu14") (class "Default")
      (node (ref "C26") (pin "1") (pinfunction "1_1") (pintype "passive"))
      (node (ref "D10") (pin "2") (pinfunction "K_2") (pintype "passive"))
      (node (ref "R75") (pin "2") (pinfunction "2_2") (pintype "passive"))
      (node (ref "R76") (pin "2") (pinfunction "2_2") (pintype "passive"))
      (node (ref "U10") (pin "15") (pinfunction "X2_15") (pintype "bidirectional"))
    )
    (net (code "63") (name "/Vs") (class "Default")
      (node (ref "R71") (pin "2") (pinfunction "2_2") (pintype "passive"))
    )
    (net (code "64") (name "GND") (class "Default")
      (node (ref "C10") (pin "2") (pinfunction "2_2") (pintype "passive"))
      (node (ref "C12") (pin "1") (pinfunction "1_1") (pintype "passive"))
      (node (ref "C13") (pin "2") (pinfunction "2_2") (pintype "passive"))
      (node (ref "C14") (pin "1") (pinfunction "1_1") (pintype "passive"))
      (node (ref "C15") (pin "1") (pinfunction "1_1") (pintype "passive"))
      (node (ref "C16") (pin "1") (pinfunction "1_1") (pintype "passive"))
      (node (ref "C17") (pin "1") (pinfunction "1_1") (pintype "passive"))
      (node (ref "C18") (pin "1") (pinfunction "1_1") (pintype "passive"))
      (node (ref "C19") (pin "1") (pinfunction "1_1") (pintype "passive"))
      (node (ref "C20") (pin "1") (pinfunction "1_1") (pintype "passive"))
      (node (ref "C23") (pin "2") (pinfunction "2_2") (pintype "passive"))
      (node (ref "C24") (pin "2") (pinfunction "2_2") (pintype "passive"))
      (node (ref "C25") (pin "1") (pinfunction "1_1") (pintype "passive"))
      (node (ref "C26") (pin "2") (pinfunction "2_2") (pintype "passive"))
      (node (ref "C28") (pin "2") (pinfunction "2_2") (pintype "passive"))
      (node (ref "C37") (pin "2") (pinfunction "2_2") (pintype "passive"))
      (node (ref "C38") (pin "2") (pinfunction "2_2") (pintype "passive"))
      (node (ref "C39") (pin "2") (pinfunction "2_2") (pintype "passive"))
      (node (ref "C4") (pin "2") (pinfunction "2_2") (pintype "passive"))
      (node (ref "C40") (pin "2") (pinfunction "2_2") (pintype "passive"))
      (node (ref "C5") (pin "2") (pinfunction "2_2") (pintype "passive"))
      (node (ref "C6") (pin "2") (pinfunction "2_2") (pintype "passive"))
      (node (ref "C62") (pin "1") (pinfunction "1_1") (pintype "passive"))
      (node (ref "C63") (pin "1") (pinfunction "1_1") (pintype "passive"))
      (node (ref "C64") (pin "1") (pinfunction "1_1") (pintype "passive"))
      (node (ref "C65") (pin "1") (pinfunction "1_1") (pintype "passive"))
      (node (ref "C66") (pin "2") (pinfunction "2_2") (pintype "passive"))
      (node (ref "C7") (pin "2") (pinfunction "2_2") (pintype "passive"))
      (node (ref "C8") (pin "2") (pinfunction "2_2") (pintype "passive"))
      (node (ref "C9") (pin "2") (pinfunction "2_2") (pintype "passive"))
      (node (ref "D10") (pin "1") (pinfunction "A_1") (pintype "passive"))
      (node (ref "D11") (pin "1") (pinfunction "A_1") (pintype "passive"))
      (node (ref "D12") (pin "1") (pinfunction "A_1") (pintype "passive"))
      (node (ref "D13") (pin "1") (pinfunction "A_1") (pintype "passive"))
      (node (ref "D3") (pin "1") (pinfunction "A_1") (pintype "passive"))
      (node (ref "D4") (pin "1") (pinfunction "A_1") (pintype "passive"))
      (node (ref "D6") (pin "1") (pinfunction "A_1") (pintype "passive"))
      (node (ref "D7") (pin "1") (pinfunction "A_1") (pintype "passive"))
      (node (ref "D8") (pin "1") (pinfunction "A_1") (pintype "passive"))
      (node (ref "D9") (pin "1") (pinfunction "A_1") (pintype "passive"))
      (node (ref "Q1") (pin "2") (pinfunction "S_2") (pintype "passive"))
      (node (ref "Q6") (pin "2") (pinfunction "E_2") (pintype "passive"))
      (node (ref "Q7") (pin "1") (pinfunction "S_1") (pintype "passive"))
      (node (ref "Q7") (pin "3") (pinfunction "S_3") (pintype "passive"))
      (node (ref "Q8") (pin "1") (pinfunction "S_1") (pintype "passive"))
      (node (ref "Q8") (pin "3") (pinfunction "S_3") (pintype "passive"))
      (node (ref "Q9") (pin "1") (pinfunction "S_1") (pintype "passive"))
      (node (ref "Q9") (pin "3") (pinfunction "S_3") (pintype "passive"))
      (node (ref "R1") (pin "1") (pinfunction "1_1") (pintype "passive"))
      (node (ref "R127") (pin "1") (pinfunction "1_1") (pintype "passive"))
      (node (ref "R24") (pin "2") (pinfunction "2_2") (pintype "passive"))
      (node (ref "R26") (pin "2") (pinfunction "2_2") (pintype "passive"))
      (node (ref "R28") (pin "2") (pinfunction "2_2") (pintype "passive"))
      (node (ref "R32") (pin "2") (pinfunction "2_2") (pintype "passive"))
      (node (ref "R34") (pin "1") (pinfunction "1_1") (pintype "passive"))
      (node (ref "R35") (pin "2") (pinfunction "2_2") (pintype "passive"))
      (node (ref "R39") (pin "1") (pinfunction "1_1") (pintype "passive"))
      (node (ref "R40") (pin "2") (pinfunction "2_2") (pintype "passive"))
      (node (ref "R48") (pin "1") (pinfunction "1_1") (pintype "passive"))
      (node (ref "R55") (pin "1") (pinfunction "1_1") (pintype "passive"))
      (node (ref "R59") (pin "1") (pinfunction "1_1") (pintype "passive"))
      (node (ref "R69") (pin "1") (pinfunction "1_1") (pintype "passive"))
      (node (ref "R70") (pin "1") (pinfunction "1_1") (pintype "passive"))
      (node (ref "R74") (pin "1") (pinfunction "1_1") (pintype "passive"))
      (node (ref "R76") (pin "1") (pinfunction "1_1") (pintype "passive"))
      (node (ref "R77") (pin "1") (pinfunction "1_1") (pintype "passive"))
      (node (ref "R78") (pin "1") (pinfunction "1_1") (pintype "passive"))
      (node (ref "R81") (pin "1") (pinfunction "1_1") (pintype "passive"))
      (node (ref "R82") (pin "1") (pinfunction "1_1") (pintype "passive"))
      (node (ref "U10") (pin "6") (pinfunction "INH_6") (pintype "input"))
      (node (ref "U10") (pin "7") (pinfunction "VEE_7") (pintype "power_in"))
      (node (ref "U10") (pin "8") (pinfunction "VSS_8") (pintype "power_in"))
      (node (ref "U6") (pin "6") (pinfunction "INH_6") (pintype "input"))
      (node (ref "U6") (pin "7") (pinfunction "VEE_7") (pintype "power_in"))
      (node (ref "U6") (pin "8") (pinfunction "VSS_8") (pintype "power_in"))
    )
    (net (code "65") (name "Net-(C12-Pad2)") (class "Default")
      (node (ref "C12") (pin "2") (pinfunction "2_2") (pintype "passive"))
      (node (ref "K1") (pin "3") (pinfunction "3_3") (pintype "passive"))
      (node (ref "R60") (pin "1") (pinfunction "1_1") (pintype "passive"))
      (node (ref "R61") (pin "1") (pinfunction "1_1") (pintype "passive"))
    )
    (net (code "66") (name "Net-(C14-Pad2)") (class "Default")
      (node (ref "C14") (pin "2") (pinfunction "2_2") (pintype "passive"))
      (node (ref "K1") (pin "1") (pinfunction "1_1") (pintype "passive"))
      (node (ref "R64") (pin "1") (pinfunction "1_1") (pintype "passive"))
      (node (ref "R65") (pin "1") (pinfunction "1_1") (pintype "passive"))
    )
    (net (code "67") (name "Net-(C62-Pad2)") (class "Default")
      (node (ref "C62") (pin "2") (pinfunction "2_2") (pintype "passive"))
      (node (ref "K2") (pin "3") (pinfunction "3_3") (pintype "passive"))
      (node (ref "R121") (pin "1") (pinfunction "1_1") (pintype "passive"))
      (node (ref "R13") (pin "1") (pinfunction "1_1") (pintype "passive"))
    )
    (net (code "68") (name "Net-(C63-Pad2)") (class "Default")
      (node (ref "C63") (pin "2") (pinfunction "2_2") (pintype "passive"))
      (node (ref "K2") (pin "1") (pinfunction "1_1") (pintype "passive"))
      (node (ref "R124") (pin "1") (pinfunction "1_1") (pintype "passive"))
      (node (ref "R125") (pin "1") (pinfunction "1_1") (pintype "passive"))
    )
    (net (code "69") (name "Net-(D5-A)") (class "Default")
      (node (ref "D5") (pin "1") (pinfunction "A_1") (pintype "passive"))
      (node (ref "K1") (pin "5") (pinfunction "5_5") (pintype "passive"))
      (node (ref "K2") (pin "5") (pinfunction "5_5") (pintype "passive"))
      (node (ref "Q6") (pin "3") (pinfunction "C_3") (pintype "passive"))
    )
    (net (code "70") (name "Net-(Q1-G)") (class "Default")
      (node (ref "Q1") (pin "1") (pinfunction "G_1") (pintype "passive"))
      (node (ref "R1") (pin "2") (pinfunction "2_2") (pintype "passive"))
      (node (ref "R84") (pin "2") (pinfunction "2_2") (pintype "passive"))
    )
    (net (code "71") (name "Net-(Q6-B)") (class "Default")
      (node (ref "Q6") (pin "1") (pinfunction "B_1") (pintype "passive"))
      (node (ref "R72") (pin "2") (pinfunction "2_2") (pintype "passive"))
      (node (ref "R74") (pin "2") (pinfunction "2_2") (pintype "passive"))
    )
    (net (code "72") (name "Net-(Q7A-G)") (class "Default")
      (node (ref "Q7") (pin "2") (pinfunction "G_2") (pintype "passive"))
      (node (ref "R31") (pin "2") (pinfunction "2_2") (pintype "passive"))
      (node (ref "R34") (pin "2") (pinfunction "2_2") (pintype "passive"))
    )
    (net (code "73") (name "Net-(Q7B-G)") (class "Default")
      (node (ref "Q7") (pin "4") (pinfunction "G_4") (pintype "passive"))
      (node (ref "R38") (pin "2") (pinfunction "2_2") (pintype "passive"))
      (node (ref "R39") (pin "2") (pinfunction "2_2") (pintype "passive"))
    )
    (net (code "74") (name "Net-(Q8A-G)") (class "Default")
      (node (ref "Q8") (pin "2") (pinfunction "G_2") (pintype "passive"))
      (node (ref "R30") (pin "2") (pinfunction "2_2") (pintype "passive"))
      (node (ref "R77") (pin "2") (pinfunction "2_2") (pintype "passive"))
    )
    (net (code "75") (name "Net-(Q8B-G)") (class "Default")
      (node (ref "Q8") (pin "4") (pinfunction "G_4") (pintype "passive"))
      (node (ref "R37") (pin "2") (pinfunction "2_2") (pintype "passive"))
      (node (ref "R78") (pin "2") (pinfunction "2_2") (pintype "passive"))
    )
    (net (code "76") (name "Net-(Q9A-G)") (class "Default")
      (node (ref "Q9") (pin "2") (pinfunction "G_2") (pintype "passive"))
      (node (ref "R79") (pin "2") (pinfunction "2_2") (pintype "passive"))
      (node (ref "R81") (pin "2") (pinfunction "2_2") (pintype "passive"))
    )
    (net (code "77") (name "Net-(Q9B-G)") (class "Default")
      (node (ref "Q9") (pin "4") (pinfunction "G_4") (pintype "passive"))
      (node (ref "R80") (pin "2") (pinfunction "2_2") (pintype "passive"))
      (node (ref "R82") (pin "2") (pinfunction "2_2") (pintype "passive"))
    )
    (net (code "78") (name "Net-(U2-IN+)") (class "Default")
      (node (ref "C66") (pin "1") (pinfunction "1_1") (pintype "passive"))
      (node (ref "R125") (pin "2") (pinfunction "2_2") (pintype "passive"))
      (node (ref "R127") (pin "2") (pinfunction "2_2") (pintype "passive"))
      (node (ref "U2") (pin "3") (pinfunction "IN+_3") (pintype "input"))
    )
    (net (code "79") (name "Net-(U2-IN-)") (class "Default")
      (node (ref "C61") (pin "2") (pinfunction "2_2") (pintype "passive"))
      (node (ref "R12") (pin "1") (pinfunction "1_1") (pintype "passive"))
      (node (ref "R121") (pin "2") (pinfunction "2_2") (pintype "passive"))
      (node (ref "U2") (pin "2") (pinfunction "IN-_2") (pintype "input"))
    )
    (net (code "80") (name "Net-(U2-OUT)") (class "Default")
      (node (ref "C61") (pin "1") (pinfunction "1_1") (pintype "passive"))
      (node (ref "C64") (pin "2") (pinfunction "2_2") (pintype "passive"))
      (node (ref "R12") (pin "2") (pinfunction "2_2") (pintype "passive"))
      (node (ref "R122") (pin "1") (pinfunction "1_1") (pintype "passive"))
      (node (ref "U2") (pin "6") (pinfunction "OUT_6") (pintype "output"))
    )
    (net (code "81") (name "Net-(U9-IN+)") (class "Default")
      (node (ref "C23") (pin "1") (pinfunction "1_1") (pintype "passive"))
      (node (ref "R65") (pin "2") (pinfunction "2_2") (pintype "passive"))
      (node (ref "R69") (pin "2") (pinfunction "2_2") (pintype "passive"))
      (node (ref "U9") (pin "3") (pinfunction "IN+_3") (pintype "input"))
    )
    (net (code "82") (name "Net-(U9-IN-)") (class "Default")
      (node (ref "C11") (pin "2") (pinfunction "2_2") (pintype "passive"))
      (node (ref "R57") (pin "1") (pinfunction "1_1") (pintype "passive"))
      (node (ref "R61") (pin "2") (pinfunction "2_2") (pintype "passive"))
      (node (ref "U9") (pin "2") (pinfunction "IN-_2") (pintype "input"))
    )
    (net (code "83") (name "Net-(U9-OUT)") (class "Default")
      (node (ref "C11") (pin "1") (pinfunction "1_1") (pintype "passive"))
      (node (ref "C15") (pin "2") (pinfunction "2_2") (pintype "passive"))
      (node (ref "R57") (pin "2") (pinfunction "2_2") (pintype "passive"))
      (node (ref "R62") (pin "1") (pinfunction "1_1") (pintype "passive"))
      (node (ref "U9") (pin "6") (pinfunction "OUT_6") (pintype "output"))
    )
    (net (code "84") (name "Vref") (class "Default")
      (node (ref "C20") (pin "2") (pinfunction "2_2") (pintype "passive"))
      (node (ref "C25") (pin "2") (pinfunction "2_2") (pintype "passive"))
      (node (ref "R126") (pin "2") (pinfunction "2_2") (pintype "passive"))
      (node (ref "R66") (pin "2") (pinfunction "2_2") (pintype "passive"))
    )
    (net (code "85") (name "unconnected-(K1-Pad2)") (class "Default")
      (node (ref "K1") (pin "2") (pinfunction "2_2") (pintype "passive"))
    )
    (net (code "86") (name "unconnected-(K2-Pad2)") (class "Default")
      (node (ref "K2") (pin "2") (pinfunction "2_2") (pintype "passive"))
    )
    (net (code "87") (name "unconnected-(U2-NC-Pad5)") (class "Default")
      (node (ref "U2") (pin "5") (pinfunction "NC_5") (pintype "passive"))
    )
    (net (code "88") (name "unconnected-(U2-VOSTRIM-Pad1)") (class "Default")
      (node (ref "U2") (pin "1") (pinfunction "VOSTRIM_1") (pintype "passive"))
    )
    (net (code "89") (name "unconnected-(U2-VOSTRIM-Pad8)") (class "Default")
      (node (ref "U2") (pin "8") (pinfunction "VOSTRIM_8") (pintype "passive"))
    )
    (net (code "90") (name "unconnected-(U9-NC-Pad5)") (class "Default")
      (node (ref "U9") (pin "5") (pinfunction "NC_5") (pintype "passive"))
    )
    (net (code "91") (name "unconnected-(U9-VOSTRIM-Pad1)") (class "Default")
      (node (ref "U9") (pin "1") (pinfunction "VOSTRIM_1") (pintype "passive"))
    )
    (net (code "92") (name "unconnected-(U9-VOSTRIM-Pad8)") (class "Default")
      (node (ref "U9") (pin "8") (pinfunction "VOSTRIM_8") (pintype "passive"))
    )
  )
)
